# IN_12A.net
KiCad netlist of a schematic drawn in Altium Designer
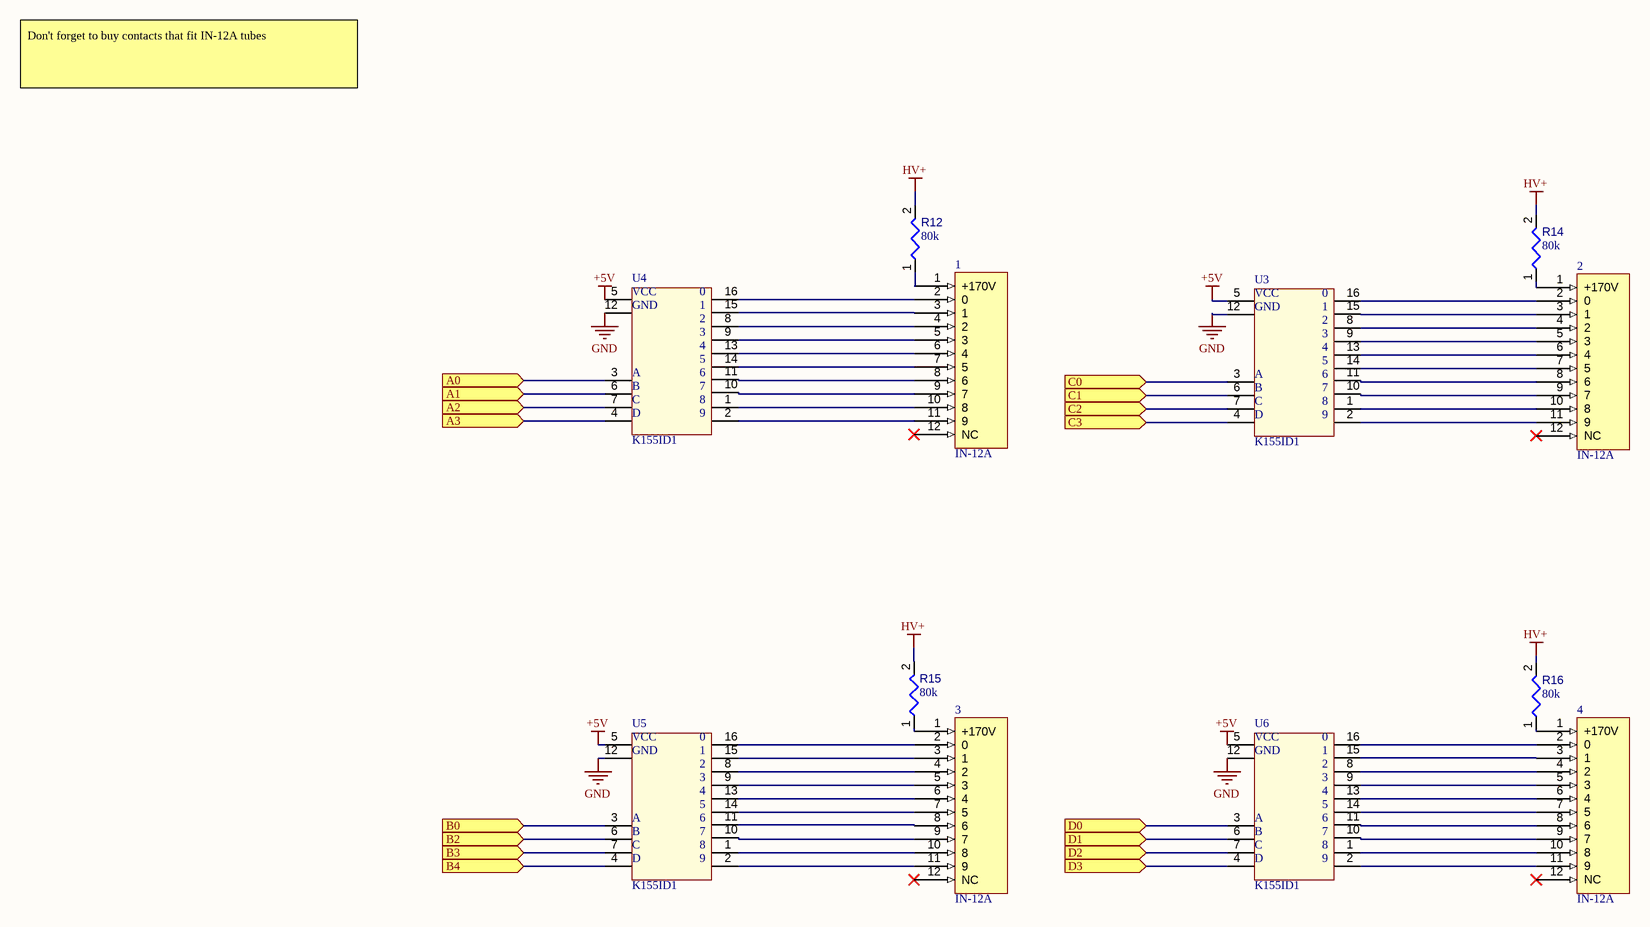
[diagram p0: IN_12A.SchDoc]

(export (version "E")
  (design (tool "Eeschema 10.0.6"))
  (components
    (comp (ref "1") (value "IN-12A") (footprint "IN-12A") (libsource (lib "HV_LIB") (part "IN-12A")))
    (comp (ref "2") (value "IN-12A") (footprint "IN-12A") (libsource (lib "HV_LIB") (part "IN-12A")))
    (comp (ref "3") (value "IN-12A") (footprint "IN-12A") (libsource (lib "HV_LIB") (part "IN-12A")))
    (comp (ref "4") (value "IN-12A") (footprint "IN-12A") (libsource (lib "HV_LIB") (part "IN-12A")))
    (comp (ref "R12")
      (value "80k")
      (footprint "RESC3216X60X45ML15T20")
      (description "Chip Resistor, 80 KOhm, +/- 1%, 0.25 W, -55 to 155 degC, 1206 (3216 Metric)")
      (fields (field (name "POWER") "250mW") (field (name "TOLERANCE") "1%"))
      (libsource (lib "University of California Riverside - FSAE") (part "RES-2"))
    )
    (comp (ref "R14")
      (value "80k")
      (footprint "RESC3216X60X45ML15T20")
      (description "Chip Resistor, 80 KOhm, +/- 1%, 0.25 W, -55 to 155 degC, 1206 (3216 Metric)")
      (fields (field (name "POWER") "250mW") (field (name "TOLERANCE") "1%"))
      (libsource (lib "University of California Riverside - FSAE") (part "RES-2"))
    )
    (comp (ref "R15")
      (value "80k")
      (footprint "RESC3216X60X45ML15T20")
      (description "Chip Resistor, 80 KOhm, +/- 1%, 0.25 W, -55 to 155 degC, 1206 (3216 Metric)")
      (fields (field (name "POWER") "250mW") (field (name "TOLERANCE") "1%"))
      (libsource (lib "University of California Riverside - FSAE") (part "RES-2"))
    )
    (comp (ref "R16")
      (value "80k")
      (footprint "RESC3216X60X45ML15T20")
      (description "Chip Resistor, 80 KOhm, +/- 1%, 0.25 W, -55 to 155 degC, 1206 (3216 Metric)")
      (fields (field (name "POWER") "250mW") (field (name "TOLERANCE") "1%"))
      (libsource (lib "University of California Riverside - FSAE") (part "RES-2"))
    )
    (comp (ref "U3")
      (value "K155ID1")
      (footprint "Socket_DIP_16")
      (libsource (lib "HV_LIB") (part "K155ID1"))
    )
    (comp (ref "U4")
      (value "K155ID1")
      (footprint "Socket_DIP_16")
      (libsource (lib "HV_LIB") (part "K155ID1"))
    )
    (comp (ref "U5")
      (value "K155ID1")
      (footprint "Socket_DIP_16")
      (libsource (lib "HV_LIB") (part "K155ID1"))
    )
    (comp (ref "U6")
      (value "K155ID1")
      (footprint "Socket_DIP_16")
      (libsource (lib "HV_LIB") (part "K155ID1"))
    )
  )
  (nets
    (net (code "1") (name "+5V") (class "Default")
      (node (ref "U3") (pin "5") (pinfunction "5_5") (pintype "passive"))
      (node (ref "U4") (pin "5") (pinfunction "5_5") (pintype "passive"))
      (node (ref "U5") (pin "5") (pinfunction "5_5") (pintype "passive"))
      (node (ref "U6") (pin "5") (pinfunction "5_5") (pintype "passive"))
    )
    (net (code "2") (name "/A0") (class "Default")
      (node (ref "U4") (pin "3") (pinfunction "3_3") (pintype "passive"))
    )
    (net (code "3") (name "/A1") (class "Default")
      (node (ref "U4") (pin "6") (pinfunction "6_6") (pintype "passive"))
    )
    (net (code "4") (name "/A2") (class "Default")
      (node (ref "U4") (pin "7") (pinfunction "7_7") (pintype "passive"))
    )
    (net (code "5") (name "/A3") (class "Default")
      (node (ref "U4") (pin "4") (pinfunction "4_4") (pintype "passive"))
    )
    (net (code "6") (name "/B0") (class "Default")
      (node (ref "U5") (pin "3") (pinfunction "3_3") (pintype "passive"))
    )
    (net (code "7") (name "/B2") (class "Default")
      (node (ref "U5") (pin "6") (pinfunction "6_6") (pintype "passive"))
    )
    (net (code "8") (name "/B3") (class "Default")
      (node (ref "U5") (pin "7") (pinfunction "7_7") (pintype "passive"))
    )
    (net (code "9") (name "/B4") (class "Default")
      (node (ref "U5") (pin "4") (pinfunction "4_4") (pintype "passive"))
    )
    (net (code "10") (name "/C0") (class "Default")
      (node (ref "U3") (pin "3") (pinfunction "3_3") (pintype "passive"))
    )
    (net (code "11") (name "/C1") (class "Default")
      (node (ref "U3") (pin "6") (pinfunction "6_6") (pintype "passive"))
    )
    (net (code "12") (name "/C2") (class "Default")
      (node (ref "U3") (pin "7") (pinfunction "7_7") (pintype "passive"))
    )
    (net (code "13") (name "/C3") (class "Default")
      (node (ref "U3") (pin "4") (pinfunction "4_4") (pintype "passive"))
    )
    (net (code "14") (name "/D0") (class "Default")
      (node (ref "U6") (pin "3") (pinfunction "3_3") (pintype "passive"))
    )
    (net (code "15") (name "/D1") (class "Default")
      (node (ref "U6") (pin "6") (pinfunction "6_6") (pintype "passive"))
    )
    (net (code "16") (name "/D2") (class "Default")
      (node (ref "U6") (pin "7") (pinfunction "7_7") (pintype "passive"))
    )
    (net (code "17") (name "/D3") (class "Default")
      (node (ref "U6") (pin "4") (pinfunction "4_4") (pintype "passive"))
    )
    (net (code "18") (name "GND") (class "Default")
      (node (ref "U3") (pin "12") (pinfunction "12_12") (pintype "passive"))
      (node (ref "U4") (pin "12") (pinfunction "12_12") (pintype "passive"))
      (node (ref "U5") (pin "12") (pinfunction "12_12") (pintype "passive"))
      (node (ref "U6") (pin "12") (pinfunction "12_12") (pintype "passive"))
    )
    (net (code "19") (name "HV+") (class "Default")
      (node (ref "R12") (pin "2") (pinfunction "2_2") (pintype "passive"))
      (node (ref "R14") (pin "2") (pinfunction "2_2") (pintype "passive"))
      (node (ref "R15") (pin "2") (pinfunction "2_2") (pintype "passive"))
      (node (ref "R16") (pin "2") (pinfunction "2_2") (pintype "passive"))
    )
    (net (code "20") (name "Net-(1-+170V)") (class "Default")
      (node (ref "1") (pin "1") (pinfunction "+170V_1") (pintype "input"))
      (node (ref "R12") (pin "1") (pinfunction "1_1") (pintype "passive"))
    )
    (net (code "21") (name "Net-(1-0)") (class "Default")
      (node (ref "1") (pin "2") (pinfunction "0_2") (pintype "input"))
      (node (ref "U4") (pin "16") (pinfunction "16_16") (pintype "passive"))
    )
    (net (code "22") (name "Net-(1-1)") (class "Default")
      (node (ref "1") (pin "3") (pinfunction "1_3") (pintype "input"))
      (node (ref "U4") (pin "15") (pinfunction "15_15") (pintype "passive"))
    )
    (net (code "23") (name "Net-(1-2)") (class "Default")
      (node (ref "1") (pin "4") (pinfunction "2_4") (pintype "input"))
      (node (ref "U4") (pin "8") (pinfunction "8_8") (pintype "passive"))
    )
    (net (code "24") (name "Net-(1-3)") (class "Default")
      (node (ref "1") (pin "5") (pinfunction "3_5") (pintype "input"))
      (node (ref "U4") (pin "9") (pinfunction "9_9") (pintype "passive"))
    )
    (net (code "25") (name "Net-(1-4)") (class "Default")
      (node (ref "1") (pin "6") (pinfunction "4_6") (pintype "input"))
      (node (ref "U4") (pin "13") (pinfunction "13_13") (pintype "passive"))
    )
    (net (code "26") (name "Net-(1-5)") (class "Default")
      (node (ref "1") (pin "7") (pinfunction "5_7") (pintype "input"))
      (node (ref "U4") (pin "14") (pinfunction "14_14") (pintype "passive"))
    )
    (net (code "27") (name "Net-(1-6)") (class "Default")
      (node (ref "1") (pin "8") (pinfunction "6_8") (pintype "input"))
      (node (ref "U4") (pin "11") (pinfunction "11_11") (pintype "passive"))
    )
    (net (code "28") (name "Net-(1-7)") (class "Default")
      (node (ref "1") (pin "9") (pinfunction "7_9") (pintype "input"))
      (node (ref "U4") (pin "10") (pinfunction "10_10") (pintype "passive"))
    )
    (net (code "29") (name "Net-(1-8)") (class "Default")
      (node (ref "1") (pin "10") (pinfunction "8_10") (pintype "input"))
      (node (ref "U4") (pin "1") (pinfunction "1_1") (pintype "passive"))
    )
    (net (code "30") (name "Net-(1-9)") (class "Default")
      (node (ref "1") (pin "11") (pinfunction "9_11") (pintype "input"))
      (node (ref "U4") (pin "2") (pinfunction "2_2") (pintype "passive"))
    )
    (net (code "31") (name "Net-(2-+170V)") (class "Default")
      (node (ref "2") (pin "1") (pinfunction "+170V_1") (pintype "input"))
      (node (ref "R14") (pin "1") (pinfunction "1_1") (pintype "passive"))
    )
    (net (code "32") (name "Net-(2-0)") (class "Default")
      (node (ref "2") (pin "2") (pinfunction "0_2") (pintype "input"))
      (node (ref "U3") (pin "16") (pinfunction "16_16") (pintype "passive"))
    )
    (net (code "33") (name "Net-(2-1)") (class "Default")
      (node (ref "2") (pin "3") (pinfunction "1_3") (pintype "input"))
      (node (ref "U3") (pin "15") (pinfunction "15_15") (pintype "passive"))
    )
    (net (code "34") (name "Net-(2-2)") (class "Default")
      (node (ref "2") (pin "4") (pinfunction "2_4") (pintype "input"))
      (node (ref "U3") (pin "8") (pinfunction "8_8") (pintype "passive"))
    )
    (net (code "35") (name "Net-(2-3)") (class "Default")
      (node (ref "2") (pin "5") (pinfunction "3_5") (pintype "input"))
      (node (ref "U3") (pin "9") (pinfunction "9_9") (pintype "passive"))
    )
    (net (code "36") (name "Net-(2-4)") (class "Default")
      (node (ref "2") (pin "6") (pinfunction "4_6") (pintype "input"))
      (node (ref "U3") (pin "13") (pinfunction "13_13") (pintype "passive"))
    )
    (net (code "37") (name "Net-(2-5)") (class "Default")
      (node (ref "2") (pin "7") (pinfunction "5_7") (pintype "input"))
      (node (ref "U3") (pin "14") (pinfunction "14_14") (pintype "passive"))
    )
    (net (code "38") (name "Net-(2-6)") (class "Default")
      (node (ref "2") (pin "8") (pinfunction "6_8") (pintype "input"))
      (node (ref "U3") (pin "11") (pinfunction "11_11") (pintype "passive"))
    )
    (net (code "39") (name "Net-(2-7)") (class "Default")
      (node (ref "2") (pin "9") (pinfunction "7_9") (pintype "input"))
      (node (ref "U3") (pin "10") (pinfunction "10_10") (pintype "passive"))
    )
    (net (code "40") (name "Net-(2-8)") (class "Default")
      (node (ref "2") (pin "10") (pinfunction "8_10") (pintype "input"))
      (node (ref "U3") (pin "1") (pinfunction "1_1") (pintype "passive"))
    )
    (net (code "41") (name "Net-(2-9)") (class "Default")
      (node (ref "2") (pin "11") (pinfunction "9_11") (pintype "input"))
      (node (ref "U3") (pin "2") (pinfunction "2_2") (pintype "passive"))
    )
    (net (code "42") (name "Net-(3-+170V)") (class "Default")
      (node (ref "3") (pin "1") (pinfunction "+170V_1") (pintype "input"))
      (node (ref "R15") (pin "1") (pinfunction "1_1") (pintype "passive"))
    )
    (net (code "43") (name "Net-(3-0)") (class "Default")
      (node (ref "3") (pin "2") (pinfunction "0_2") (pintype "input"))
      (node (ref "U5") (pin "16") (pinfunction "16_16") (pintype "passive"))
    )
    (net (code "44") (name "Net-(3-1)") (class "Default")
      (node (ref "3") (pin "3") (pinfunction "1_3") (pintype "input"))
      (node (ref "U5") (pin "15") (pinfunction "15_15") (pintype "passive"))
    )
    (net (code "45") (name "Net-(3-2)") (class "Default")
      (node (ref "3") (pin "4") (pinfunction "2_4") (pintype "input"))
      (node (ref "U5") (pin "8") (pinfunction "8_8") (pintype "passive"))
    )
    (net (code "46") (name "Net-(3-3)") (class "Default")
      (node (ref "3") (pin "5") (pinfunction "3_5") (pintype "input"))
      (node (ref "U5") (pin "9") (pinfunction "9_9") (pintype "passive"))
    )
    (net (code "47") (name "Net-(3-4)") (class "Default")
      (node (ref "3") (pin "6") (pinfunction "4_6") (pintype "input"))
      (node (ref "U5") (pin "13") (pinfunction "13_13") (pintype "passive"))
    )
    (net (code "48") (name "Net-(3-5)") (class "Default")
      (node (ref "3") (pin "7") (pinfunction "5_7") (pintype "input"))
      (node (ref "U5") (pin "14") (pinfunction "14_14") (pintype "passive"))
    )
    (net (code "49") (name "Net-(3-6)") (class "Default")
      (node (ref "3") (pin "8") (pinfunction "6_8") (pintype "input"))
      (node (ref "U5") (pin "11") (pinfunction "11_11") (pintype "passive"))
    )
    (net (code "50") (name "Net-(3-7)") (class "Default")
      (node (ref "3") (pin "9") (pinfunction "7_9") (pintype "input"))
      (node (ref "U5") (pin "10") (pinfunction "10_10") (pintype "passive"))
    )
    (net (code "51") (name "Net-(3-8)") (class "Default")
      (node (ref "3") (pin "10") (pinfunction "8_10") (pintype "input"))
      (node (ref "U5") (pin "1") (pinfunction "1_1") (pintype "passive"))
    )
    (net (code "52") (name "Net-(3-9)") (class "Default")
      (node (ref "3") (pin "11") (pinfunction "9_11") (pintype "input"))
      (node (ref "U5") (pin "2") (pinfunction "2_2") (pintype "passive"))
    )
    (net (code "53") (name "Net-(4-+170V)") (class "Default")
      (node (ref "4") (pin "1") (pinfunction "+170V_1") (pintype "input"))
      (node (ref "R16") (pin "1") (pinfunction "1_1") (pintype "passive"))
    )
    (net (code "54") (name "Net-(4-0)") (class "Default")
      (node (ref "4") (pin "2") (pinfunction "0_2") (pintype "input"))
      (node (ref "U6") (pin "16") (pinfunction "16_16") (pintype "passive"))
    )
    (net (code "55") (name "Net-(4-1)") (class "Default")
      (node (ref "4") (pin "3") (pinfunction "1_3") (pintype "input"))
      (node (ref "U6") (pin "15") (pinfunction "15_15") (pintype "passive"))
    )
    (net (code "56") (name "Net-(4-2)") (class "Default")
      (node (ref "4") (pin "4") (pinfunction "2_4") (pintype "input"))
      (node (ref "U6") (pin "8") (pinfunction "8_8") (pintype "passive"))
    )
    (net (code "57") (name "Net-(4-3)") (class "Default")
      (node (ref "4") (pin "5") (pinfunction "3_5") (pintype "input"))
      (node (ref "U6") (pin "9") (pinfunction "9_9") (pintype "passive"))
    )
    (net (code "58") (name "Net-(4-4)") (class "Default")
      (node (ref "4") (pin "6") (pinfunction "4_6") (pintype "input"))
      (node (ref "U6") (pin "13") (pinfunction "13_13") (pintype "passive"))
    )
    (net (code "59") (name "Net-(4-5)") (class "Default")
      (node (ref "4") (pin "7") (pinfunction "5_7") (pintype "input"))
      (node (ref "U6") (pin "14") (pinfunction "14_14") (pintype "passive"))
    )
    (net (code "60") (name "Net-(4-6)") (class "Default")
      (node (ref "4") (pin "8") (pinfunction "6_8") (pintype "input"))
      (node (ref "U6") (pin "11") (pinfunction "11_11") (pintype "passive"))
    )
    (net (code "61") (name "Net-(4-7)") (class "Default")
      (node (ref "4") (pin "9") (pinfunction "7_9") (pintype "input"))
      (node (ref "U6") (pin "10") (pinfunction "10_10") (pintype "passive"))
    )
    (net (code "62") (name "Net-(4-8)") (class "Default")
      (node (ref "4") (pin "10") (pinfunction "8_10") (pintype "input"))
      (node (ref "U6") (pin "1") (pinfunction "1_1") (pintype "passive"))
    )
    (net (code "63") (name "Net-(4-9)") (class "Default")
      (node (ref "4") (pin "11") (pinfunction "9_11") (pintype "input"))
      (node (ref "U6") (pin "2") (pinfunction "2_2") (pintype "passive"))
    )
    (net (code "64") (name "unconnected-(1-NC-Pad12)") (class "Default")
      (node (ref "1") (pin "12") (pinfunction "NC_12") (pintype "input+no_connect"))
    )
    (net (code "65") (name "unconnected-(2-NC-Pad12)") (class "Default")
      (node (ref "2") (pin "12") (pinfunction "NC_12") (pintype "input+no_connect"))
    )
    (net (code "66") (name "unconnected-(3-NC-Pad12)") (class "Default")
      (node (ref "3") (pin "12") (pinfunction "NC_12") (pintype "input+no_connect"))
    )
    (net (code "67") (name "unconnected-(4-NC-Pad12)") (class "Default")
      (node (ref "4") (pin "12") (pinfunction "NC_12") (pintype "input+no_connect"))
    )
  )
)
